# rolety.net
KiCad netlist of a schematic drawn in EAGLE
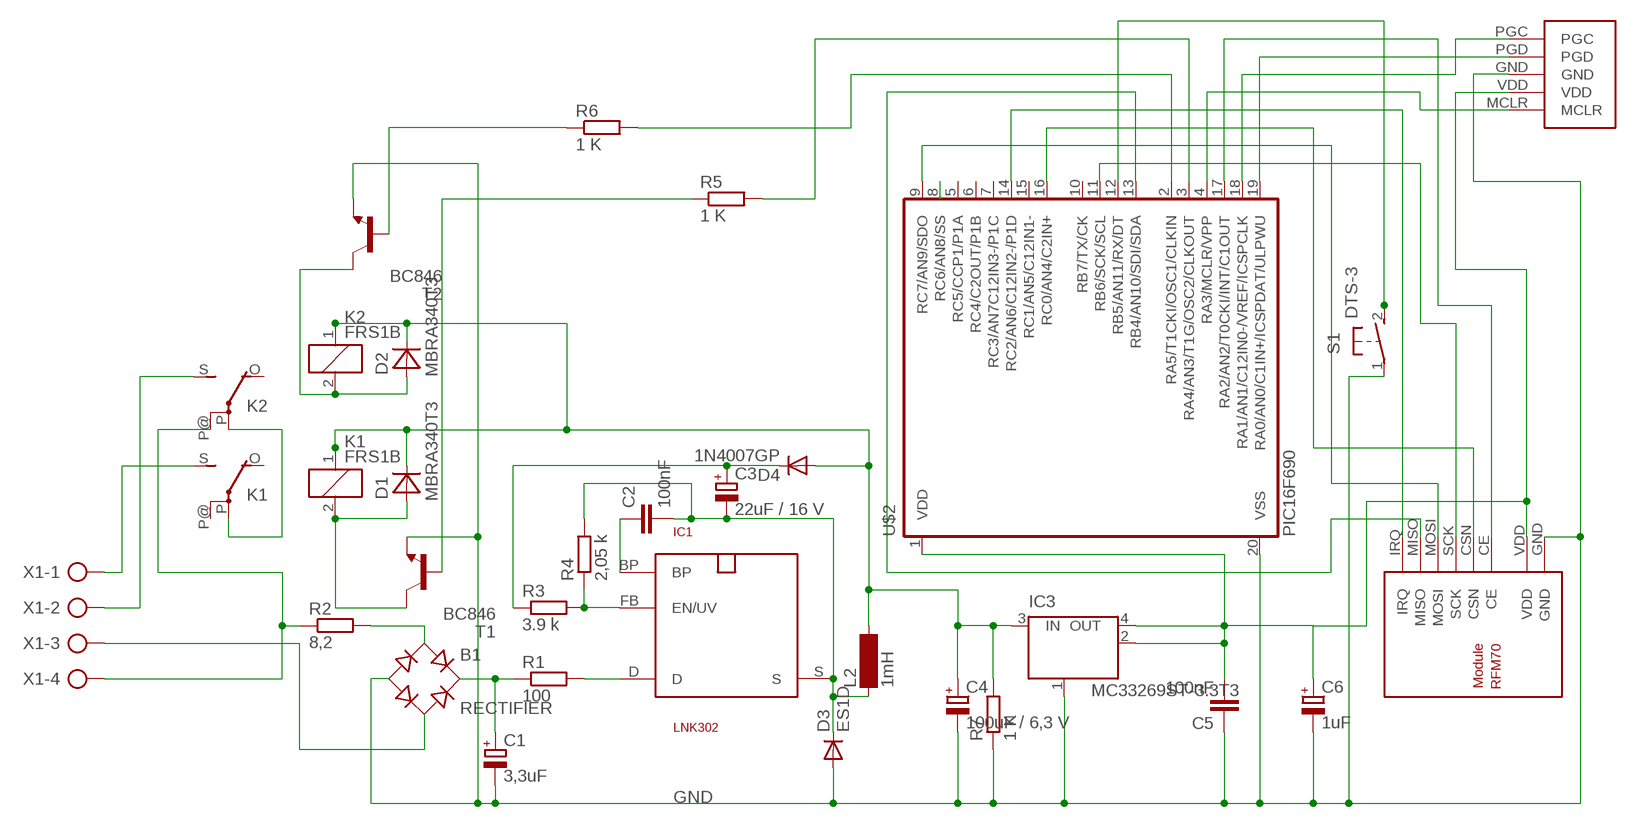
[diagram p0: schematic, sheet 1]

(export (version "E")
  (design (tool "Eeschema 10.0.6"))
  (components
    (comp (ref "B1")
      (value "RECTIFIER")
      (footprint "eagle-import:TO-269AA")
      (libsource (lib "eagle-import") (part "RECTIFIER-S40"))
    )
    (comp (ref "C1")
      (value "3,3uF")
      (footprint "eagle-import:E5-10,5")
      (libsource (lib "eagle-import") (part "CPOL-EUE5-10.5"))
    )
    (comp (ref "C2")
      (value "100nF")
      (footprint "eagle-import:C2012")
      (libsource (lib "eagle-import") (part "C-EUC2012"))
    )
    (comp (ref "C3")
      (value "22uF / 16 V")
      (footprint "eagle-import:SMC_C")
      (libsource (lib "eagle-import") (part "CPOL-EUSMCC"))
    )
    (comp (ref "C4")
      (value "100uF / 6,3 V")
      (footprint "eagle-import:E2,5-5")
      (libsource (lib "eagle-import") (part "CPOL-EUE2.5-5"))
    )
    (comp (ref "C5")
      (value "100nF")
      (footprint "eagle-import:C2012")
      (libsource (lib "eagle-import") (part "C-EUC2012"))
    )
    (comp (ref "C6")
      (value "1uF")
      (footprint "eagle-import:SMC_A")
      (libsource (lib "eagle-import") (part "CPOL-EUSMCA"))
    )
    (comp (ref "D1")
      (value "MBRA340T3")
      (footprint "eagle-import:SMA")
      (libsource (lib "eagle-import") (part "MBRA340T3"))
    )
    (comp (ref "D2")
      (value "MBRA340T3")
      (footprint "eagle-import:SMA")
      (libsource (lib "eagle-import") (part "MBRA340T3"))
    )
    (comp (ref "D3")
      (value "ES1D")
      (footprint "eagle-import:DO214AC")
      (libsource (lib "eagle-import") (part "DIODE-DO214AC"))
    )
    (comp (ref "D4")
      (value "1N4007GP")
      (footprint "eagle-import:DO214AA")
      (libsource (lib "eagle-import") (part "DIODE-DO214AA"))
    )
    (comp (ref "IC1")
      (value "LNK302")
      (footprint "eagle-import:SO-8C")
      (libsource (lib "eagle-import") (part "SO-8C"))
    )
    (comp (ref "IC3")
      (value "MC33269ST-3.3T3")
      (footprint "eagle-import:SOT223")
      (libsource (lib "eagle-import") (part "MC33269ST-3.3T3"))
    )
    (comp (ref "K1")
      (value "FRS1B")
      (footprint "eagle-import:FRS1B")
      (libsource (lib "eagle-import") (part "FRS1B"))
    )
    (comp (ref "K2")
      (value "FRS1B")
      (footprint "eagle-import:FRS1B")
      (fields (field (name "OC_FARNELL") "unknown") (field (name "OC_NEWARK") "unknown"))
      (libsource (lib "eagle-import") (part "FRS1B"))
    )
    (comp (ref "L2")
      (value "1mH")
      (footprint "eagle-import:BS11")
      (libsource (lib "eagle-import") (part "BS11"))
    )
    (comp (ref "R1")
      (value "100")
      (footprint "eagle-import:R2512W")
      (libsource (lib "eagle-import") (part "R-EU_R2512W"))
    )
    (comp (ref "R2")
      (value "8,2")
      (footprint "eagle-import:0411_12")
      (libsource (lib "eagle-import") (part "R-EU_0411/12"))
    )
    (comp (ref "R3")
      (value "3.9 k")
      (footprint "eagle-import:M2012")
      (libsource (lib "eagle-import") (part "R-EU_M2012"))
    )
    (comp (ref "R4")
      (value "2,05 k")
      (footprint "eagle-import:M2012")
      (libsource (lib "eagle-import") (part "R-EU_M2012"))
    )
    (comp (ref "R5")
      (value "1 K")
      (footprint "eagle-import:M2012")
      (libsource (lib "eagle-import") (part "R-EU_M2012"))
    )
    (comp (ref "R6")
      (value "1 K")
      (footprint "eagle-import:M2012")
      (libsource (lib "eagle-import") (part "R-EU_M2012"))
    )
    (comp (ref "R7")
      (value "1 K")
      (footprint "eagle-import:M2012")
      (libsource (lib "eagle-import") (part "R-EU_M2012"))
    )
    (comp (ref "S1")
      (value "DTS-3")
      (footprint "eagle-import:DTS-3")
      (libsource (lib "eagle-import") (part "DTS-3"))
    )
    (comp (ref "T1")
      (value "BC846")
      (footprint "eagle-import:SOT23")
      (libsource (lib "eagle-import") (part "BC846"))
    )
    (comp (ref "T2")
      (value "BC846")
      (footprint "eagle-import:SOT23")
      (libsource (lib "eagle-import") (part "BC846"))
    )
    (comp (ref "U$1")
      (value "RFM70")
      (footprint "eagle-import:RFM70")
      (libsource (lib "eagle-import") (part "RFM70"))
    )
    (comp (ref "U$2")
      (value "PIC16F690")
      (footprint "eagle-import:SSOP20")
      (libsource (lib "eagle-import") (part "PIC16F690"))
    )
    (comp (ref "U$3")
      (value "PROGRAMMINGHEADERDIP")
      (footprint "eagle-import:PROGHEADER")
      (libsource (lib "eagle-import") (part "PROGRAMMINGHEADERDIP"))
    )
    (comp (ref "X1")
      (value "AK500/4")
      (footprint "eagle-import:AK500_4")
      (libsource (lib "eagle-import") (part "AK500/4"))
    )
  )
  (nets
    (net (code "1") (name "/GND") (class "Default")
      (node (ref "B1") (pin "-") (pinfunction "-_-") (pintype "passive"))
      (node (ref "C1") (pin "-") (pinfunction "-_-") (pintype "passive"))
      (node (ref "C4") (pin "-") (pinfunction "-_-") (pintype "passive"))
      (node (ref "C5") (pin "1") (pinfunction "1_1") (pintype "passive"))
      (node (ref "C6") (pin "-") (pinfunction "-_-") (pintype "passive"))
      (node (ref "D3") (pin "A") (pinfunction "A_A") (pintype "passive"))
      (node (ref "IC3") (pin "1") (pinfunction "GND/ADJ_1") (pintype "input"))
      (node (ref "R7") (pin "1") (pinfunction "1_1") (pintype "passive"))
      (node (ref "S1") (pin "1") (pinfunction "1_1") (pintype "passive"))
      (node (ref "T1") (pin "2") (pinfunction "E_2") (pintype "passive"))
      (node (ref "T2") (pin "2") (pinfunction "E_2") (pintype "passive"))
      (node (ref "U$1") (pin "GND") (pinfunction "GND_GND") (pintype "power_in"))
      (node (ref "U$2") (pin "20") (pinfunction "VSS_20") (pintype "power_in"))
      (node (ref "U$3") (pin "GND") (pinfunction "GND_GND") (pintype "power_in"))
    )
    (net (code "2") (name "Net-(B1-Pad+)") (class "Default")
      (node (ref "B1") (pin "+") (pinfunction "+_+") (pintype "passive"))
      (node (ref "C1") (pin "+") (pinfunction "+_+") (pintype "passive"))
      (node (ref "R1") (pin "1") (pinfunction "1_1") (pintype "passive"))
    )
    (net (code "3") (name "Net-(B1-PadAC1)") (class "Default")
      (node (ref "B1") (pin "AC1") (pinfunction "AC1_AC1") (pintype "passive"))
      (node (ref "R2") (pin "2") (pinfunction "2_2") (pintype "passive"))
    )
    (net (code "4") (name "Net-(C2-Pad1)") (class "Default")
      (node (ref "C2") (pin "1") (pinfunction "1_1") (pintype "passive"))
      (node (ref "IC1") (pin "BP") (pinfunction "BP_BP") (pintype "passive"))
    )
    (net (code "5") (name "Net-(C2-Pad2)") (class "Default")
      (node (ref "C2") (pin "2") (pinfunction "2_2") (pintype "passive"))
      (node (ref "C3") (pin "-") (pinfunction "-_-") (pintype "passive"))
      (node (ref "D3") (pin "C") (pinfunction "C_C") (pintype "passive"))
      (node (ref "IC1") (pin "S") (pinfunction "S_S") (pintype "power_in"))
      (node (ref "L2") (pin "1") (pinfunction "1_1") (pintype "passive"))
      (node (ref "R4") (pin "2") (pinfunction "2_2") (pintype "passive"))
    )
    (net (code "6") (name "Net-(C3-Pad+)") (class "Default")
      (node (ref "C3") (pin "+") (pinfunction "+_+") (pintype "passive"))
      (node (ref "D4") (pin "C") (pinfunction "C_C") (pintype "passive"))
      (node (ref "R3") (pin "1") (pinfunction "1_1") (pintype "passive"))
    )
    (net (code "7") (name "Net-(IC1-EN{slash}UV)") (class "Default")
      (node (ref "IC1") (pin "FB") (pinfunction "EN/UV_FB") (pintype "input"))
      (node (ref "R3") (pin "2") (pinfunction "2_2") (pintype "passive"))
      (node (ref "R4") (pin "1") (pinfunction "1_1") (pintype "passive"))
    )
    (net (code "8") (name "Net-(IC1-PadD)") (class "Default")
      (node (ref "IC1") (pin "D") (pinfunction "D_D") (pintype "open_collector"))
      (node (ref "R1") (pin "2") (pinfunction "2_2") (pintype "passive"))
    )
    (net (code "9") (name "Net-(IC3-IN)") (class "Default")
      (node (ref "C4") (pin "+") (pinfunction "+_+") (pintype "passive"))
      (node (ref "D1") (pin "C") (pinfunction "C_C") (pintype "passive"))
      (node (ref "D2") (pin "C") (pinfunction "C_C") (pintype "passive"))
      (node (ref "D4") (pin "A") (pinfunction "A_A") (pintype "passive"))
      (node (ref "IC3") (pin "3") (pinfunction "IN_3") (pintype "input"))
      (node (ref "K1") (pin "1") (pinfunction "1_1") (pintype "passive"))
      (node (ref "K2") (pin "1") (pinfunction "1_1") (pintype "passive"))
      (node (ref "L2") (pin "2") (pinfunction "2_2") (pintype "passive"))
      (node (ref "R7") (pin "2") (pinfunction "2_2") (pintype "passive"))
    )
    (net (code "10") (name "Net-(K1-PadP)") (class "Default")
      (node (ref "K1") (pin "P") (pinfunction "P_P") (pintype "passive"))
      (node (ref "K2") (pin "P") (pinfunction "P_P") (pintype "passive"))
    )
    (net (code "11") (name "Net-(T1-B)") (class "Default")
      (node (ref "R5") (pin "1") (pinfunction "1_1") (pintype "passive"))
      (node (ref "T1") (pin "1") (pinfunction "B_1") (pintype "passive"))
    )
    (net (code "12") (name "Net-(T1-C)") (class "Default")
      (node (ref "D1") (pin "A") (pinfunction "A_A") (pintype "passive"))
      (node (ref "K1") (pin "2") (pinfunction "2_2") (pintype "passive"))
      (node (ref "T1") (pin "3") (pinfunction "C_3") (pintype "passive"))
    )
    (net (code "13") (name "Net-(T2-B)") (class "Default")
      (node (ref "R6") (pin "1") (pinfunction "1_1") (pintype "passive"))
      (node (ref "T2") (pin "1") (pinfunction "B_1") (pintype "passive"))
    )
    (net (code "14") (name "Net-(T2-C)") (class "Default")
      (node (ref "D2") (pin "A") (pinfunction "A_A") (pintype "passive"))
      (node (ref "K2") (pin "2") (pinfunction "2_2") (pintype "passive"))
      (node (ref "T2") (pin "3") (pinfunction "C_3") (pintype "passive"))
    )
    (net (code "15") (name "Net-(U$2-RA0{slash}AN0{slash}C1IN+{slash}ICSPDAT{slash}ULPWU)") (class "Default")
      (node (ref "U$2") (pin "19") (pinfunction "RA0/AN0/C1IN+/ICSPDAT/ULPWU_19") (pintype "bidirectional"))
      (node (ref "U$3") (pin "PGD") (pinfunction "PGD_PGD") (pintype "bidirectional"))
    )
    (net (code "16") (name "Net-(U$2-RA1{slash}AN1{slash}C12IN0-{slash}VREF{slash}ICSPCLK)") (class "Default")
      (node (ref "U$2") (pin "18") (pinfunction "RA1/AN1/C12IN0-/VREF/ICSPCLK_18") (pintype "bidirectional"))
      (node (ref "U$3") (pin "PGC") (pinfunction "PGC_PGC") (pintype "bidirectional"))
    )
    (net (code "17") (name "Net-(U$2-RA2{slash}AN2{slash}T0CKI{slash}INT{slash}C1OUT)") (class "Default")
      (node (ref "U$1") (pin "CE") (pinfunction "CE_CE") (pintype "bidirectional"))
      (node (ref "U$2") (pin "17") (pinfunction "RA2/AN2/T0CKI/INT/C1OUT_17") (pintype "bidirectional"))
    )
    (net (code "18") (name "Net-(U$2-RA3{slash}MCLR{slash}VPP)") (class "Default")
      (node (ref "U$2") (pin "4") (pinfunction "RA3/MCLR/VPP_4") (pintype "bidirectional"))
      (node (ref "U$3") (pin "MCLR") (pinfunction "MCLR_MCLR") (pintype "output"))
    )
    (net (code "19") (name "Net-(U$2-RA4{slash}AN3{slash}T1G{slash}OSC2{slash}CLKOUT)") (class "Default")
      (node (ref "R5") (pin "2") (pinfunction "2_2") (pintype "passive"))
      (node (ref "U$2") (pin "3") (pinfunction "RA4/AN3/T1G/OSC2/CLKOUT_3") (pintype "bidirectional"))
    )
    (net (code "20") (name "Net-(U$2-RA5{slash}T1CKI{slash}OSC1{slash}CLKIN)") (class "Default")
      (node (ref "R6") (pin "2") (pinfunction "2_2") (pintype "passive"))
      (node (ref "U$2") (pin "2") (pinfunction "RA5/T1CKI/OSC1/CLKIN_2") (pintype "bidirectional"))
    )
    (net (code "21") (name "Net-(U$2-RB4{slash}AN10{slash}SDI{slash}SDA)") (class "Default")
      (node (ref "U$1") (pin "MISO") (pinfunction "MISO_MISO") (pintype "bidirectional"))
      (node (ref "U$2") (pin "13") (pinfunction "RB4/AN10/SDI/SDA_13") (pintype "bidirectional"))
    )
    (net (code "22") (name "Net-(U$2-RB5{slash}AN11{slash}RX{slash}DT)") (class "Default")
      (node (ref "S1") (pin "2") (pinfunction "2_2") (pintype "passive"))
      (node (ref "U$2") (pin "12") (pinfunction "RB5/AN11/RX/DT_12") (pintype "bidirectional"))
    )
    (net (code "23") (name "Net-(U$2-RB6{slash}SCK{slash}SCL)") (class "Default")
      (node (ref "U$1") (pin "SCK") (pinfunction "SCK_SCK") (pintype "bidirectional"))
      (node (ref "U$2") (pin "11") (pinfunction "RB6/SCK/SCL_11") (pintype "bidirectional"))
    )
    (net (code "24") (name "Net-(U$2-RC0{slash}AN4{slash}C2IN+)") (class "Default")
      (node (ref "U$1") (pin "CSN") (pinfunction "CSN_CSN") (pintype "bidirectional"))
      (node (ref "U$2") (pin "16") (pinfunction "RC0/AN4/C2IN+_16") (pintype "bidirectional"))
    )
    (net (code "25") (name "Net-(U$2-RC2{slash}AN6{slash}C12IN2-{slash}P1D)") (class "Default")
      (node (ref "U$1") (pin "IRQ") (pinfunction "IRQ_IRQ") (pintype "bidirectional"))
      (node (ref "U$2") (pin "14") (pinfunction "RC2/AN6/C12IN2-/P1D_14") (pintype "bidirectional"))
    )
    (net (code "26") (name "Net-(U$2-RC7{slash}AN9{slash}SDO)") (class "Default")
      (node (ref "U$1") (pin "MOSI") (pinfunction "MOSI_MOSI") (pintype "bidirectional"))
      (node (ref "U$2") (pin "9") (pinfunction "RC7/AN9/SDO_9") (pintype "bidirectional"))
    )
    (net (code "27") (name "Net-(U$2-VDD)") (class "Default")
      (node (ref "C5") (pin "2") (pinfunction "2_2") (pintype "passive"))
      (node (ref "C6") (pin "+") (pinfunction "+_+") (pintype "passive"))
      (node (ref "IC3") (pin "2") (pinfunction "OUT_2") (pintype "passive"))
      (node (ref "IC3") (pin "4") (pinfunction "OUT_4") (pintype "passive"))
      (node (ref "U$1") (pin "VDD") (pinfunction "VDD_VDD") (pintype "power_in"))
      (node (ref "U$2") (pin "1") (pinfunction "VDD_1") (pintype "power_in"))
      (node (ref "U$3") (pin "VDD") (pinfunction "VDD_VDD") (pintype "power_in"))
    )
    (net (code "28") (name "Net-(X1A-KL)") (class "Default")
      (node (ref "K1") (pin "S") (pinfunction "S_S") (pintype "passive"))
      (node (ref "X1") (pin "1") (pinfunction "KL_1") (pintype "passive"))
    )
    (net (code "29") (name "Net-(X1B-KL)") (class "Default")
      (node (ref "K2") (pin "S") (pinfunction "S_S") (pintype "passive"))
      (node (ref "X1") (pin "2") (pinfunction "KL_2") (pintype "passive"))
    )
    (net (code "30") (name "Net-(X1C-KL)") (class "Default")
      (node (ref "B1") (pin "AC2") (pinfunction "AC2_AC2") (pintype "passive"))
      (node (ref "X1") (pin "3") (pinfunction "KL_3") (pintype "passive"))
    )
    (net (code "31") (name "Net-(X1D-KL)") (class "Default")
      (node (ref "K2") (pin "P@") (pinfunction "P_P@") (pintype "passive"))
      (node (ref "R2") (pin "1") (pinfunction "1_1") (pintype "passive"))
      (node (ref "X1") (pin "4") (pinfunction "KL_4") (pintype "passive"))
    )
    (net (code "32") (name "unconnected-(K1-PadO)") (class "Default")
      (node (ref "K1") (pin "O") (pinfunction "O_O") (pintype "passive"))
    )
    (net (code "33") (name "unconnected-(K1B-P-PadP@)") (class "Default")
      (node (ref "K1") (pin "P@") (pinfunction "P_P@") (pintype "passive"))
    )
    (net (code "34") (name "unconnected-(K2-PadO)") (class "Default")
      (node (ref "K2") (pin "O") (pinfunction "O_O") (pintype "passive"))
    )
    (net (code "35") (name "unconnected-(U$2-RB7{slash}TX{slash}CK-Pad10)") (class "Default")
      (node (ref "U$2") (pin "10") (pinfunction "RB7/TX/CK_10") (pintype "bidirectional"))
    )
    (net (code "36") (name "unconnected-(U$2-RC1{slash}AN5{slash}C12IN1--Pad15)") (class "Default")
      (node (ref "U$2") (pin "15") (pinfunction "RC1/AN5/C12IN1-_15") (pintype "bidirectional"))
    )
    (net (code "37") (name "unconnected-(U$2-RC3{slash}AN7C12IN3-{slash}P1C-Pad7)") (class "Default")
      (node (ref "U$2") (pin "7") (pinfunction "RC3/AN7C12IN3-/P1C_7") (pintype "bidirectional"))
    )
    (net (code "38") (name "unconnected-(U$2-RC4{slash}C2OUT{slash}P1B-Pad6)") (class "Default")
      (node (ref "U$2") (pin "6") (pinfunction "RC4/C2OUT/P1B_6") (pintype "bidirectional"))
    )
    (net (code "39") (name "unconnected-(U$2-RC5{slash}CCP1{slash}P1A-Pad5)") (class "Default")
      (node (ref "U$2") (pin "5") (pinfunction "RC5/CCP1/P1A_5") (pintype "bidirectional"))
    )
    (net (code "40") (name "unconnected-(U$2-RC6{slash}AN8{slash}SS-Pad8)") (class "Default")
      (node (ref "U$2") (pin "8") (pinfunction "RC6/AN8/SS_8") (pintype "bidirectional"))
    )
  )
)
